# MCU_board_ATmega328p_v2_4.net
KiCad netlist of a schematic drawn in EAGLE
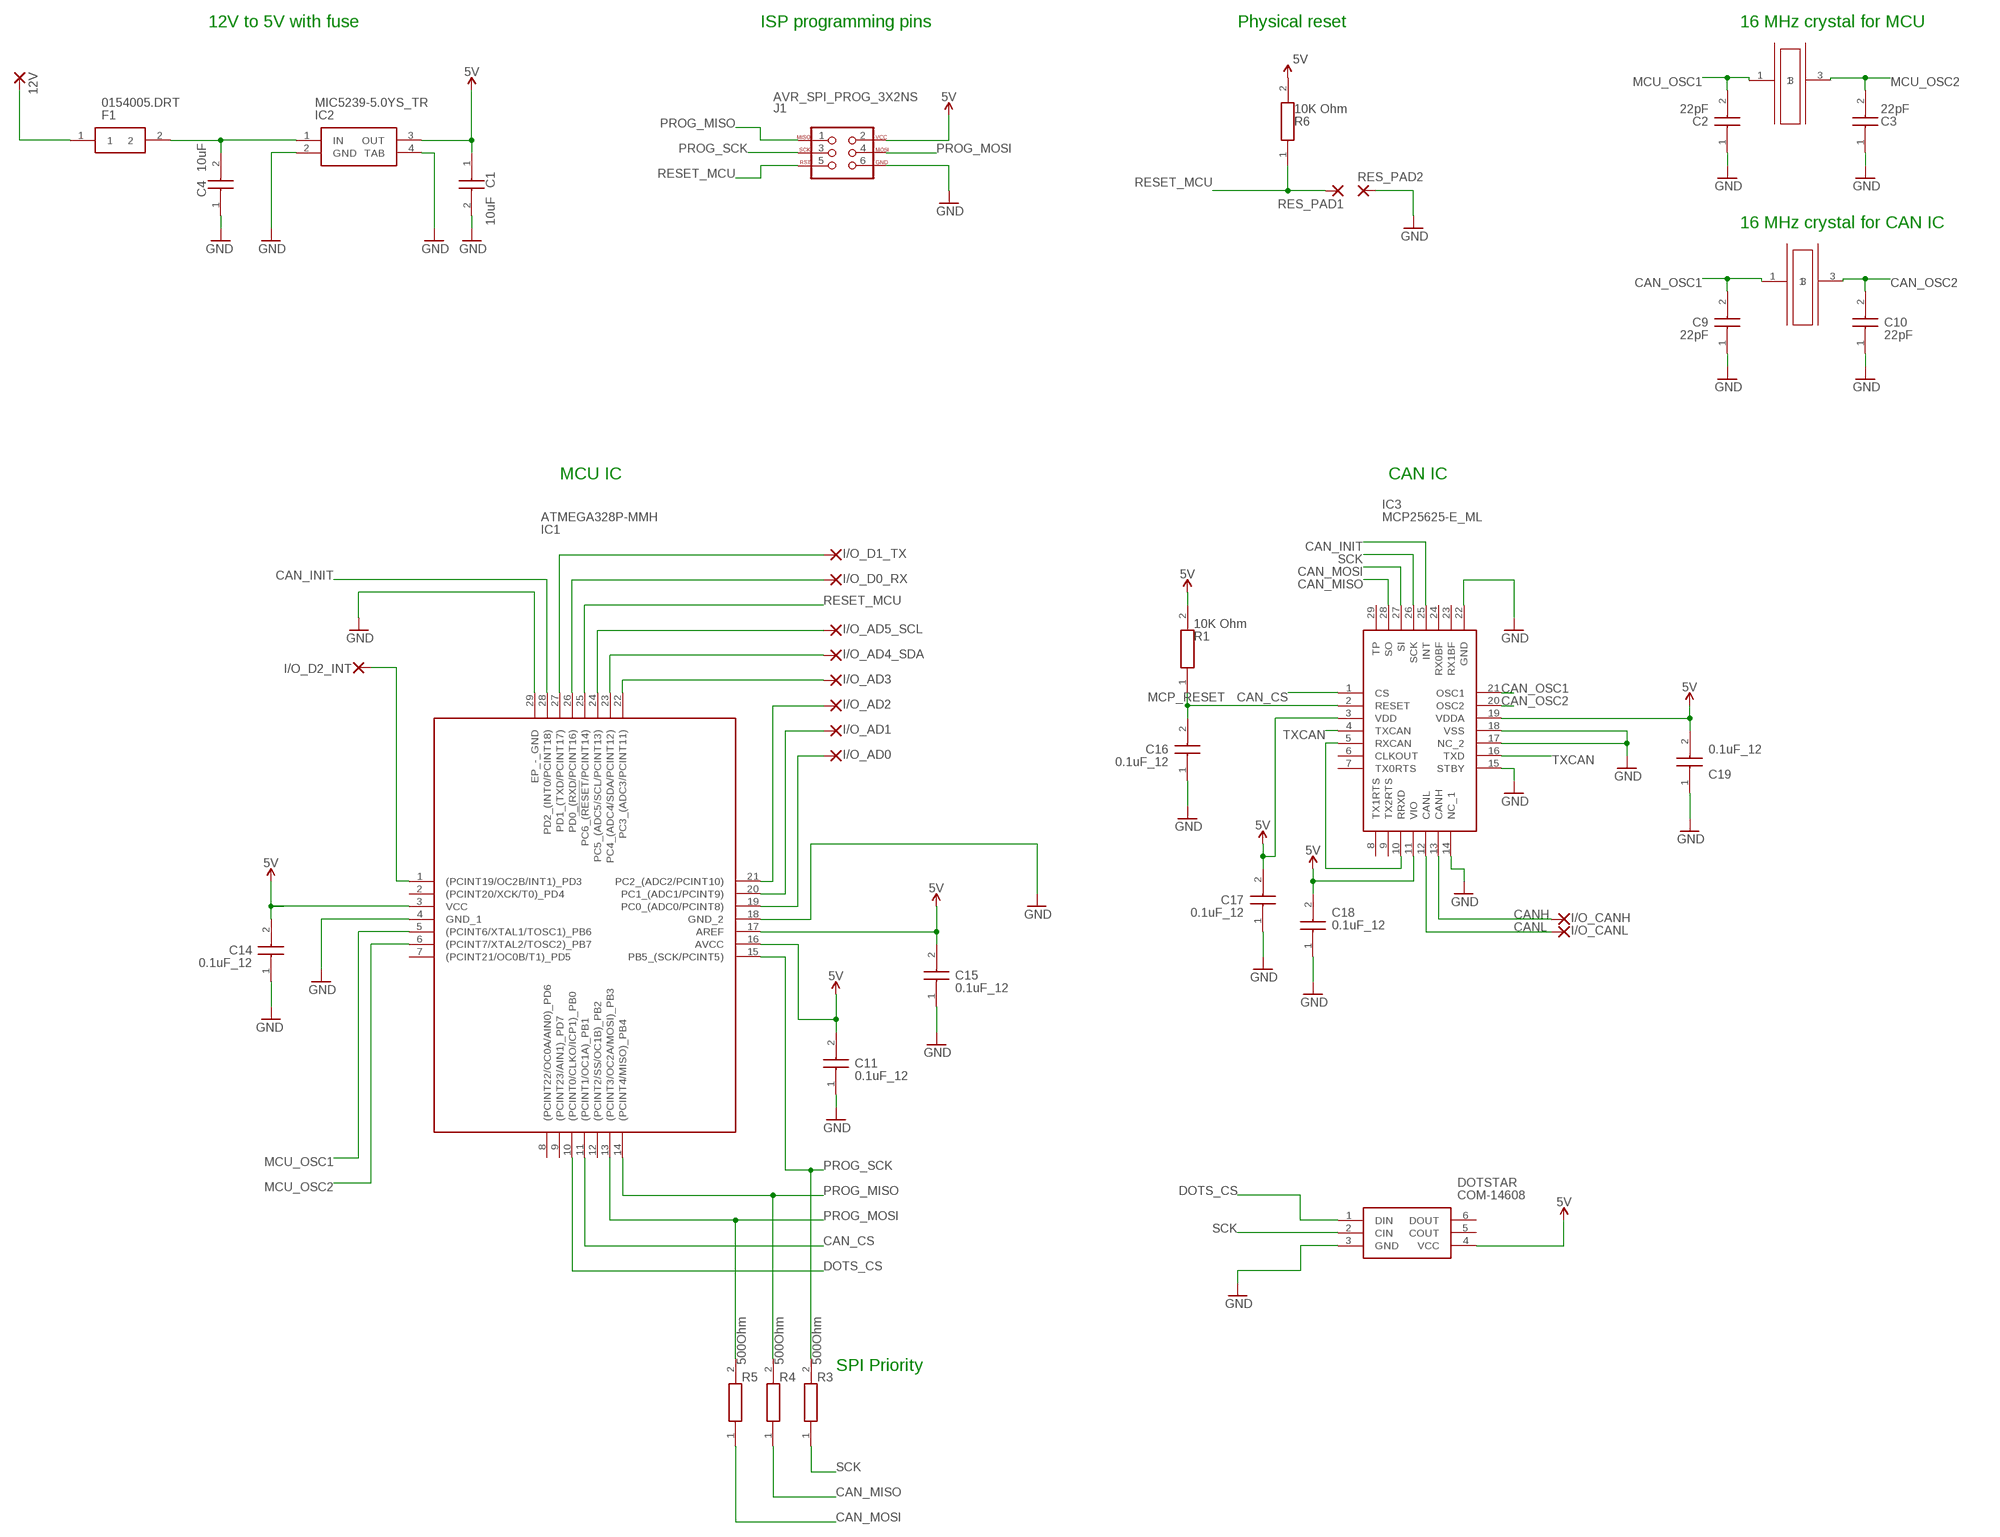
[diagram p0: schematic, sheet 1]

(export (version "E")
  (design (tool "Eeschema 10.0.6"))
  (components
    (comp (ref "12V")
      (value "2,15/1,0(HALFHOLE)H+V")
      (footprint "eagle-import:2,54_2,0(HALFHOLE)H+V")
      (libsource (lib "eagle-import") (part "2,15/1,0(HALFHOLE)H+V"))
    )
    (comp (ref "C1")
      (value "10uF")
      (footprint "eagle-import:CAPPM3216X180N")
      (fields (field (name "ARROW_PART_NUMBER") "T491A106K016AT") (field (name "RS_PART_NUMBER") "1696687"))
      (libsource (lib "eagle-import") (part "T491A106K016AT"))
    )
    (comp (ref "C2")
      (value "22pF")
      (footprint "eagle-import:CAPC3216X229N")
      (fields (field (name "ARROW_PART_NUMBER") "12066D106KAT2A") (field (name "RS_PART_NUMBER") "1356756"))
      (libsource (lib "eagle-import") (part "12066D106KAT2A"))
    )
    (comp (ref "C3")
      (value "22pF")
      (footprint "eagle-import:CAPC3216X229N")
      (fields (field (name "ARROW_PART_NUMBER") "12066D106KAT2A") (field (name "RS_PART_NUMBER") "1356756"))
      (libsource (lib "eagle-import") (part "12066D106KAT2A"))
    )
    (comp (ref "C4")
      (value "10uF")
      (footprint "eagle-import:CAPPM3216X180N")
      (fields (field (name "ARROW_PART_NUMBER") "T491A106K016AT") (field (name "RS_PART_NUMBER") "1696687"))
      (libsource (lib "eagle-import") (part "T491A106K016AT"))
    )
    (comp (ref "C9")
      (value "22pF")
      (footprint "eagle-import:CAPC3216X229N")
      (fields (field (name "ARROW_PART_NUMBER") "12066D106KAT2A") (field (name "RS_PART_NUMBER") "1356756"))
      (libsource (lib "eagle-import") (part "12066D106KAT2A"))
    )
    (comp (ref "C10")
      (value "22pF")
      (footprint "eagle-import:CAPC3216X229N")
      (fields (field (name "ARROW_PART_NUMBER") "12066D106KAT2A") (field (name "RS_PART_NUMBER") "1356756"))
      (libsource (lib "eagle-import") (part "12066D106KAT2A"))
    )
    (comp (ref "C11")
      (value "0.1uF_12")
      (footprint "eagle-import:CAPC3216X229N")
      (fields (field (name "ARROW_PART_NUMBER") "12066D106KAT2A") (field (name "RS_PART_NUMBER") "1356756"))
      (libsource (lib "eagle-import") (part "12066D106KAT2A"))
    )
    (comp (ref "C14")
      (value "0.1uF_12")
      (footprint "eagle-import:CAPC3216X229N")
      (fields (field (name "ARROW_PART_NUMBER") "12066D106KAT2A") (field (name "RS_PART_NUMBER") "1356756"))
      (libsource (lib "eagle-import") (part "12066D106KAT2A"))
    )
    (comp (ref "C15")
      (value "0.1uF_12")
      (footprint "eagle-import:CAPC3216X229N")
      (fields (field (name "ARROW_PART_NUMBER") "12066D106KAT2A") (field (name "RS_PART_NUMBER") "1356756"))
      (libsource (lib "eagle-import") (part "12066D106KAT2A"))
    )
    (comp (ref "C16")
      (value "0.1uF_12")
      (footprint "eagle-import:CAPC3216X229N")
      (fields (field (name "ARROW_PART_NUMBER") "12066D106KAT2A") (field (name "RS_PART_NUMBER") "1356756"))
      (libsource (lib "eagle-import") (part "12066D106KAT2A"))
    )
    (comp (ref "C17")
      (value "0.1uF_12")
      (footprint "eagle-import:CAPC3216X229N")
      (fields (field (name "ARROW_PART_NUMBER") "12066D106KAT2A") (field (name "RS_PART_NUMBER") "1356756"))
      (libsource (lib "eagle-import") (part "12066D106KAT2A"))
    )
    (comp (ref "C18")
      (value "0.1uF_12")
      (footprint "eagle-import:CAPC3216X229N")
      (fields (field (name "ARROW_PART_NUMBER") "12066D106KAT2A") (field (name "RS_PART_NUMBER") "1356756"))
      (libsource (lib "eagle-import") (part "12066D106KAT2A"))
    )
    (comp (ref "C19")
      (value "0.1uF_12")
      (footprint "eagle-import:CAPC3216X229N")
      (fields (field (name "ARROW_PART_NUMBER") "12066D106KAT2A") (field (name "RS_PART_NUMBER") "1356756"))
      (libsource (lib "eagle-import") (part "12066D106KAT2A"))
    )
    (comp (ref "DOTSTAR")
      (value "COM-14608")
      (footprint "eagle-import:SON75P200X200X100-6N")
      (libsource (lib "eagle-import") (part "COM-14608"))
    )
    (comp (ref "F1")
      (value "0154005.DRT")
      (footprint "eagle-import:0154001.DRT")
      (fields (field (name "RS_PART_NUMBER") "2196260P"))
      (libsource (lib "eagle-import") (part "0154005.DRT"))
    )
    (comp (ref "I/O_AD0")
      (value "2,15/1,0(HALFHOLE)H+V")
      (footprint "eagle-import:2,54_2,0(HALFHOLE)H+V")
      (libsource (lib "eagle-import") (part "2,15/1,0(HALFHOLE)H+V"))
    )
    (comp (ref "I/O_AD1")
      (value "2,15/1,0(HALFHOLE)H+V")
      (footprint "eagle-import:2,54_2,0(HALFHOLE)H+V")
      (libsource (lib "eagle-import") (part "2,15/1,0(HALFHOLE)H+V"))
    )
    (comp (ref "I/O_AD2")
      (value "2,15/1,0(HALFHOLE)H+V")
      (footprint "eagle-import:2,54_2,0(HALFHOLE)H+V")
      (libsource (lib "eagle-import") (part "2,15/1,0(HALFHOLE)H+V"))
    )
    (comp (ref "I/O_AD3")
      (value "2,15/1,0(HALFHOLE)H+V")
      (footprint "eagle-import:2,54_2,0(HALFHOLE)H+V")
      (libsource (lib "eagle-import") (part "2,15/1,0(HALFHOLE)H+V"))
    )
    (comp (ref "I/O_AD4_SDA")
      (value "2,15/1,0(HALFHOLE)H+V")
      (footprint "eagle-import:2,54_2,0(HALFHOLE)H+V")
      (libsource (lib "eagle-import") (part "2,15/1,0(HALFHOLE)H+V"))
    )
    (comp (ref "I/O_AD5_SCL")
      (value "2,15/1,0(HALFHOLE)H+V")
      (footprint "eagle-import:2,54_2,0(HALFHOLE)H+V")
      (libsource (lib "eagle-import") (part "2,15/1,0(HALFHOLE)H+V"))
    )
    (comp (ref "I/O_CANH")
      (value "2,15/1,0(HALFHOLE)H+V")
      (footprint "eagle-import:2,54_2,0(HALFHOLE)H+V")
      (libsource (lib "eagle-import") (part "2,15/1,0(HALFHOLE)H+V"))
    )
    (comp (ref "I/O_CANL")
      (value "2,15/1,0(HALFHOLE)H+V")
      (footprint "eagle-import:2,54_2,0(HALFHOLE)H+V")
      (libsource (lib "eagle-import") (part "2,15/1,0(HALFHOLE)H+V"))
    )
    (comp (ref "I/O_D0_RX")
      (value "2,15/1,0(HALFHOLE)H+V")
      (footprint "eagle-import:2,54_2,0(HALFHOLE)H+V")
      (libsource (lib "eagle-import") (part "2,15/1,0(HALFHOLE)H+V"))
    )
    (comp (ref "I/O_D1_TX")
      (value "2,15/1,0(HALFHOLE)H+V")
      (footprint "eagle-import:2,54_2,0(HALFHOLE)H+V")
      (libsource (lib "eagle-import") (part "2,15/1,0(HALFHOLE)H+V"))
    )
    (comp (ref "I/O_D2_INT")
      (value "2,15/1,0(HALFHOLE)H+V")
      (footprint "eagle-import:2,54_2,0(HALFHOLE)H+V")
      (libsource (lib "eagle-import") (part "2,15/1,0(HALFHOLE)H+V"))
    )
    (comp (ref "IC1")
      (value "ATMEGA328P-MMH")
      (footprint "eagle-import:QFN45P400X400X100-29N")
      (fields (field (name "RS_PART_NUMBER") "1310272P"))
      (libsource (lib "eagle-import") (part "ATMEGA328P-MMH"))
    )
    (comp (ref "IC2")
      (value "MIC5239-5.0YS_TR")
      (footprint "eagle-import:SOT230P700X170-4N")
      (fields
        (field (name "ARROW_PART_NUMBER") "MIC5239-5.0YS TR")
        (field (name "RS_PART_NUMBER") "7275535P")
      )
      (libsource (lib "eagle-import") (part "MIC5239-5.0YS_TR"))
    )
    (comp (ref "IC3")
      (value "MCP25625-E_ML")
      (footprint "eagle-import:QFN65P600X600X100-29N")
      (fields (field (name "ARROW_PART_NUMBER") "MCP25625-E/ML") (field (name "RS_PART_NUMBER") "1654104"))
      (libsource (lib "eagle-import") (part "MCP25625-E_ML"))
    )
    (comp (ref "J1")
      (value "AVR_SPI_PROG_3X2NS")
      (footprint "eagle-import:2X3-NS")
      (libsource (lib "eagle-import") (part "AVR_SPI_PROG_3X2NS"))
    )
    (comp (ref "R1")
      (value "10K Ohm")
      (footprint "eagle-import:RESC3116X65N")
      (fields
        (field (name "ARROW_PART_NUMBER") "CRCW120610K0FKEAHP")
        (field (name "RS_PART_NUMBER") "8121789P")
      )
      (libsource (lib "eagle-import") (part "CRCW120610K0FKEAHP"))
    )
    (comp (ref "R3")
      (value "500Ohm")
      (footprint "eagle-import:RESC3116X65N")
      (fields (field (name "ARROW_PART_NUMBER") "CRCW1206499RFKEAHP"))
      (libsource (lib "eagle-import") (part "CRCW1206499RFKEAHP"))
    )
    (comp (ref "R4")
      (value "500Ohm")
      (footprint "eagle-import:RESC3116X65N")
      (fields (field (name "ARROW_PART_NUMBER") "CRCW1206499RFKEAHP"))
      (libsource (lib "eagle-import") (part "CRCW1206499RFKEAHP"))
    )
    (comp (ref "R5")
      (value "500Ohm")
      (footprint "eagle-import:RESC3116X65N")
      (fields (field (name "ARROW_PART_NUMBER") "CRCW1206499RFKEAHP"))
      (libsource (lib "eagle-import") (part "CRCW1206499RFKEAHP"))
    )
    (comp (ref "R6")
      (value "10K Ohm")
      (footprint "eagle-import:RESC3116X65N")
      (fields
        (field (name "ARROW_PART_NUMBER") "CRCW120610K0FKEAHP")
        (field (name "RS_PART_NUMBER") "8121789P")
      )
      (libsource (lib "eagle-import") (part "CRCW120610K0FKEAHP"))
    )
    (comp (ref "RES_PAD1")
      (value "SMD2")
      (footprint "eagle-import:SMD1,27-2,54")
      (libsource (lib "eagle-import") (part "SMD2"))
    )
    (comp (ref "RES_PAD2")
      (value "SMD2")
      (footprint "eagle-import:SMD1,27-2,54")
      (libsource (lib "eagle-import") (part "SMD2"))
    )
    (comp (ref "U$1")
      (value "FA-20H")
      (footprint "eagle-import:FA-20H")
      (libsource (lib "eagle-import") (part "FA-20H"))
    )
    (comp (ref "U$2")
      (value "FA-20H")
      (footprint "eagle-import:FA-20H")
      (libsource (lib "eagle-import") (part "FA-20H"))
    )
  )
  (nets
    (net (code "1") (name "/CANH") (class "Default")
      (node (ref "I/O_CANH") (pin "P$1") (pinfunction "P_P$1") (pintype "passive"))
      (node (ref "IC3") (pin "13") (pinfunction "CANH_13") (pintype "bidirectional"))
    )
    (net (code "2") (name "/CANL") (class "Default")
      (node (ref "I/O_CANL") (pin "P$1") (pinfunction "P_P$1") (pintype "passive"))
      (node (ref "IC3") (pin "12") (pinfunction "CANL_12") (pintype "bidirectional"))
    )
    (net (code "3") (name "/CAN_CS") (class "Default")
      (node (ref "IC1") (pin "11") (pinfunction "(PCINT1/OC1A)_PB1_11") (pintype "bidirectional"))
      (node (ref "IC3") (pin "1") (pinfunction "CS_1") (pintype "input"))
    )
    (net (code "4") (name "/CAN_INIT") (class "Default")
      (node (ref "IC1") (pin "28") (pinfunction "PD2_(INT0/PCINT18)_28") (pintype "bidirectional"))
      (node (ref "IC3") (pin "25") (pinfunction "INT_25") (pintype "input"))
    )
    (net (code "5") (name "/CAN_MISO") (class "Default")
      (node (ref "IC3") (pin "28") (pinfunction "SO_28") (pintype "bidirectional"))
      (node (ref "R4") (pin "1") (pinfunction "1_1") (pintype "bidirectional"))
    )
    (net (code "6") (name "/CAN_MOSI") (class "Default")
      (node (ref "IC3") (pin "27") (pinfunction "SI_27") (pintype "bidirectional"))
      (node (ref "R5") (pin "1") (pinfunction "1_1") (pintype "bidirectional"))
    )
    (net (code "7") (name "/CAN_OSC1") (class "Default")
      (node (ref "C9") (pin "2") (pinfunction "2_2") (pintype "bidirectional"))
      (node (ref "IC3") (pin "21") (pinfunction "OSC1_21") (pintype "bidirectional"))
      (node (ref "U$1") (pin "1") (pinfunction "1_1") (pintype "bidirectional"))
    )
    (net (code "8") (name "/CAN_OSC2") (class "Default")
      (node (ref "C10") (pin "2") (pinfunction "2_2") (pintype "bidirectional"))
      (node (ref "IC3") (pin "20") (pinfunction "OSC2_20") (pintype "bidirectional"))
      (node (ref "U$1") (pin "3") (pinfunction "3_3") (pintype "bidirectional"))
    )
    (net (code "9") (name "/DOTS_CS") (class "Default")
      (node (ref "DOTSTAR") (pin "1") (pinfunction "DIN_1") (pintype "bidirectional"))
      (node (ref "IC1") (pin "10") (pinfunction "(PCINT0/CLKO/ICP1)_PB0_10") (pintype "bidirectional"))
    )
    (net (code "10") (name "/MCP_RESET") (class "Default")
      (node (ref "C16") (pin "2") (pinfunction "2_2") (pintype "bidirectional"))
      (node (ref "IC3") (pin "2") (pinfunction "RESET_2") (pintype "bidirectional"))
      (node (ref "R1") (pin "1") (pinfunction "1_1") (pintype "bidirectional"))
    )
    (net (code "11") (name "/MCU_OSC1") (class "Default")
      (node (ref "C2") (pin "2") (pinfunction "2_2") (pintype "bidirectional"))
      (node (ref "IC1") (pin "5") (pinfunction "(PCINT6/XTAL1/TOSC1)_PB6_5") (pintype "bidirectional"))
      (node (ref "U$2") (pin "1") (pinfunction "1_1") (pintype "bidirectional"))
    )
    (net (code "12") (name "/MCU_OSC2") (class "Default")
      (node (ref "C3") (pin "2") (pinfunction "2_2") (pintype "bidirectional"))
      (node (ref "IC1") (pin "6") (pinfunction "(PCINT7/XTAL2/TOSC2)_PB7_6") (pintype "bidirectional"))
      (node (ref "U$2") (pin "3") (pinfunction "3_3") (pintype "bidirectional"))
    )
    (net (code "13") (name "/PROG_MISO") (class "Default")
      (node (ref "IC1") (pin "14") (pinfunction "(PCINT4/MISO)_PB4_14") (pintype "bidirectional"))
      (node (ref "J1") (pin "1") (pinfunction "1_1") (pintype "passive"))
      (node (ref "R4") (pin "2") (pinfunction "2_2") (pintype "bidirectional"))
    )
    (net (code "14") (name "/PROG_MOSI") (class "Default")
      (node (ref "IC1") (pin "13") (pinfunction "(PCINT3/OC2A/MOSI)_PB3_13") (pintype "bidirectional"))
      (node (ref "J1") (pin "4") (pinfunction "4_4") (pintype "passive"))
      (node (ref "R5") (pin "2") (pinfunction "2_2") (pintype "bidirectional"))
    )
    (net (code "15") (name "/PROG_SCK") (class "Default")
      (node (ref "IC1") (pin "15") (pinfunction "PB5_(SCK/PCINT5)_15") (pintype "bidirectional"))
      (node (ref "J1") (pin "3") (pinfunction "3_3") (pintype "passive"))
      (node (ref "R3") (pin "2") (pinfunction "2_2") (pintype "bidirectional"))
    )
    (net (code "16") (name "/RESET_MCU") (class "Default")
      (node (ref "IC1") (pin "25") (pinfunction "PC6_(~{RESET}/PCINT14)_25") (pintype "bidirectional"))
      (node (ref "J1") (pin "5") (pinfunction "5_5") (pintype "passive"))
      (node (ref "R6") (pin "1") (pinfunction "1_1") (pintype "bidirectional"))
      (node (ref "RES_PAD1") (pin "1") (pinfunction "P_1") (pintype "passive"))
    )
    (net (code "17") (name "/SCK") (class "Default")
      (node (ref "DOTSTAR") (pin "2") (pinfunction "CIN_2") (pintype "bidirectional"))
      (node (ref "IC3") (pin "26") (pinfunction "SCK_26") (pintype "bidirectional"))
      (node (ref "R3") (pin "1") (pinfunction "1_1") (pintype "bidirectional"))
    )
    (net (code "18") (name "/TXCAN") (class "Default")
      (node (ref "IC3") (pin "16") (pinfunction "TXD_16") (pintype "bidirectional"))
      (node (ref "IC3") (pin "4") (pinfunction "TXCAN_4") (pintype "bidirectional"))
    )
    (net (code "19") (name "5V") (class "Default")
      (node (ref "C1") (pin "1") (pinfunction "K_1") (pintype "bidirectional"))
      (node (ref "C11") (pin "2") (pinfunction "2_2") (pintype "bidirectional"))
      (node (ref "C14") (pin "2") (pinfunction "2_2") (pintype "bidirectional"))
      (node (ref "C15") (pin "2") (pinfunction "2_2") (pintype "bidirectional"))
      (node (ref "C17") (pin "2") (pinfunction "2_2") (pintype "bidirectional"))
      (node (ref "C18") (pin "2") (pinfunction "2_2") (pintype "bidirectional"))
      (node (ref "C19") (pin "2") (pinfunction "2_2") (pintype "bidirectional"))
      (node (ref "DOTSTAR") (pin "4") (pinfunction "VCC_4") (pintype "bidirectional"))
      (node (ref "IC1") (pin "16") (pinfunction "AVCC_16") (pintype "bidirectional"))
      (node (ref "IC1") (pin "17") (pinfunction "AREF_17") (pintype "bidirectional"))
      (node (ref "IC1") (pin "3") (pinfunction "VCC_3") (pintype "bidirectional"))
      (node (ref "IC2") (pin "3") (pinfunction "OUT_3") (pintype "bidirectional"))
      (node (ref "IC3") (pin "11") (pinfunction "VIO_11") (pintype "bidirectional"))
      (node (ref "IC3") (pin "19") (pinfunction "VDDA_19") (pintype "power_in"))
      (node (ref "IC3") (pin "3") (pinfunction "VDD_3") (pintype "power_in"))
      (node (ref "J1") (pin "2") (pinfunction "2_2") (pintype "passive"))
      (node (ref "R1") (pin "2") (pinfunction "2_2") (pintype "bidirectional"))
      (node (ref "R6") (pin "2") (pinfunction "2_2") (pintype "bidirectional"))
    )
    (net (code "20") (name "GND") (class "Default")
      (node (ref "C1") (pin "2") (pinfunction "A_2") (pintype "bidirectional"))
      (node (ref "C10") (pin "1") (pinfunction "1_1") (pintype "bidirectional"))
      (node (ref "C11") (pin "1") (pinfunction "1_1") (pintype "bidirectional"))
      (node (ref "C14") (pin "1") (pinfunction "1_1") (pintype "bidirectional"))
      (node (ref "C15") (pin "1") (pinfunction "1_1") (pintype "bidirectional"))
      (node (ref "C16") (pin "1") (pinfunction "1_1") (pintype "bidirectional"))
      (node (ref "C17") (pin "1") (pinfunction "1_1") (pintype "bidirectional"))
      (node (ref "C18") (pin "1") (pinfunction "1_1") (pintype "bidirectional"))
      (node (ref "C19") (pin "1") (pinfunction "1_1") (pintype "bidirectional"))
      (node (ref "C2") (pin "1") (pinfunction "1_1") (pintype "bidirectional"))
      (node (ref "C3") (pin "1") (pinfunction "1_1") (pintype "bidirectional"))
      (node (ref "C4") (pin "1") (pinfunction "K_1") (pintype "bidirectional"))
      (node (ref "C9") (pin "1") (pinfunction "1_1") (pintype "bidirectional"))
      (node (ref "DOTSTAR") (pin "3") (pinfunction "GND_3") (pintype "bidirectional"))
      (node (ref "IC1") (pin "18") (pinfunction "GND_2_18") (pintype "bidirectional"))
      (node (ref "IC1") (pin "29") (pinfunction "EP_-_GND_29") (pintype "bidirectional"))
      (node (ref "IC1") (pin "4") (pinfunction "GND_1_4") (pintype "bidirectional"))
      (node (ref "IC2") (pin "2") (pinfunction "GND_2") (pintype "bidirectional"))
      (node (ref "IC2") (pin "4") (pinfunction "TAB_4") (pintype "bidirectional"))
      (node (ref "IC3") (pin "14") (pinfunction "NC_1_14") (pintype "bidirectional"))
      (node (ref "IC3") (pin "15") (pinfunction "STBY_15") (pintype "bidirectional"))
      (node (ref "IC3") (pin "17") (pinfunction "NC_2_17") (pintype "bidirectional"))
      (node (ref "IC3") (pin "18") (pinfunction "VSS_18") (pintype "power_in"))
      (node (ref "IC3") (pin "22") (pinfunction "GND_22") (pintype "power_in"))
      (node (ref "J1") (pin "6") (pinfunction "6_6") (pintype "passive"))
      (node (ref "RES_PAD2") (pin "1") (pinfunction "P_1") (pintype "passive"))
    )
    (net (code "21") (name "Net-(12V-P)") (class "Default")
      (node (ref "12V") (pin "P$1") (pinfunction "P_P$1") (pintype "passive"))
      (node (ref "F1") (pin "1") (pinfunction "1_1") (pintype "bidirectional"))
    )
    (net (code "22") (name "Net-(C4-A)") (class "Default")
      (node (ref "C4") (pin "2") (pinfunction "A_2") (pintype "bidirectional"))
      (node (ref "F1") (pin "2") (pinfunction "2_2") (pintype "bidirectional"))
      (node (ref "IC2") (pin "1") (pinfunction "IN_1") (pintype "bidirectional"))
    )
    (net (code "23") (name "Net-(I/O_AD0-P)") (class "Default")
      (node (ref "I/O_AD0") (pin "P$1") (pinfunction "P_P$1") (pintype "passive"))
      (node (ref "IC1") (pin "19") (pinfunction "PC0_(ADC0/PCINT8)_19") (pintype "bidirectional"))
    )
    (net (code "24") (name "Net-(I/O_AD1-P)") (class "Default")
      (node (ref "I/O_AD1") (pin "P$1") (pinfunction "P_P$1") (pintype "passive"))
      (node (ref "IC1") (pin "20") (pinfunction "PC1_(ADC1/PCINT9)_20") (pintype "bidirectional"))
    )
    (net (code "25") (name "Net-(I/O_AD2-P)") (class "Default")
      (node (ref "I/O_AD2") (pin "P$1") (pinfunction "P_P$1") (pintype "passive"))
      (node (ref "IC1") (pin "21") (pinfunction "PC2_(ADC2/PCINT10)_21") (pintype "bidirectional"))
    )
    (net (code "26") (name "Net-(I/O_AD3-P)") (class "Default")
      (node (ref "I/O_AD3") (pin "P$1") (pinfunction "P_P$1") (pintype "passive"))
      (node (ref "IC1") (pin "22") (pinfunction "PC3_(ADC3/PCINT11)_22") (pintype "bidirectional"))
    )
    (net (code "27") (name "Net-(I/O_AD4_SDA-P)") (class "Default")
      (node (ref "I/O_AD4_SDA") (pin "P$1") (pinfunction "P_P$1") (pintype "passive"))
      (node (ref "IC1") (pin "23") (pinfunction "PC4_(ADC4/SDA/PCINT12)_23") (pintype "bidirectional"))
    )
    (net (code "28") (name "Net-(I/O_AD5_SCL-P)") (class "Default")
      (node (ref "I/O_AD5_SCL") (pin "P$1") (pinfunction "P_P$1") (pintype "passive"))
      (node (ref "IC1") (pin "24") (pinfunction "PC5_(ADC5/SCL/PCINT13)_24") (pintype "bidirectional"))
    )
    (net (code "29") (name "Net-(I/O_D0_RX-P)") (class "Default")
      (node (ref "I/O_D0_RX") (pin "P$1") (pinfunction "P_P$1") (pintype "passive"))
      (node (ref "IC1") (pin "26") (pinfunction "PD0_(RXD/PCINT16)_26") (pintype "bidirectional"))
    )
    (net (code "30") (name "Net-(I/O_D1_TX-P)") (class "Default")
      (node (ref "I/O_D1_TX") (pin "P$1") (pinfunction "P_P$1") (pintype "passive"))
      (node (ref "IC1") (pin "27") (pinfunction "PD1_(TXD/PCINT17)_27") (pintype "bidirectional"))
    )
    (net (code "31") (name "Net-(I/O_D2_INT-P)") (class "Default")
      (node (ref "I/O_D2_INT") (pin "P$1") (pinfunction "P_P$1") (pintype "passive"))
      (node (ref "IC1") (pin "1") (pinfunction "(PCINT19/OC2B/INT1)_PD3_1") (pintype "bidirectional"))
    )
    (net (code "32") (name "Net-(IC3-RRXD)") (class "Default")
      (node (ref "IC3") (pin "10") (pinfunction "RRXD_10") (pintype "bidirectional"))
      (node (ref "IC3") (pin "5") (pinfunction "RXCAN_5") (pintype "bidirectional"))
    )
    (net (code "33") (name "unconnected-(DOTSTAR-COUT-Pad5)") (class "Default")
      (node (ref "DOTSTAR") (pin "5") (pinfunction "COUT_5") (pintype "bidirectional"))
    )
    (net (code "34") (name "unconnected-(DOTSTAR-DOUT-Pad6)") (class "Default")
      (node (ref "DOTSTAR") (pin "6") (pinfunction "DOUT_6") (pintype "bidirectional"))
    )
    (net (code "35") (name "unconnected-(IC1-(PCINT2{slash}SS{slash}OC1B)_PB2-Pad12)") (class "Default")
      (node (ref "IC1") (pin "12") (pinfunction "(PCINT2/SS/OC1B)_PB2_12") (pintype "bidirectional"))
    )
    (net (code "36") (name "unconnected-(IC1-(PCINT20{slash}XCK{slash}T0)_PD4-Pad2)") (class "Default")
      (node (ref "IC1") (pin "2") (pinfunction "(PCINT20/XCK/T0)_PD4_2") (pintype "bidirectional"))
    )
    (net (code "37") (name "unconnected-(IC1-(PCINT21{slash}OC0B{slash}T1)_PD5-Pad7)") (class "Default")
      (node (ref "IC1") (pin "7") (pinfunction "(PCINT21/OC0B/T1)_PD5_7") (pintype "bidirectional"))
    )
    (net (code "38") (name "unconnected-(IC1-(PCINT22{slash}OC0A{slash}AIN0)_PD6-Pad8)") (class "Default")
      (node (ref "IC1") (pin "8") (pinfunction "(PCINT22/OC0A/AIN0)_PD6_8") (pintype "bidirectional"))
    )
    (net (code "39") (name "unconnected-(IC1-(PCINT23{slash}AIN1)_PD7-Pad9)") (class "Default")
      (node (ref "IC1") (pin "9") (pinfunction "(PCINT23/AIN1)_PD7_9") (pintype "bidirectional"))
    )
    (net (code "40") (name "unconnected-(IC3-CLKOUT-Pad6)") (class "Default")
      (node (ref "IC3") (pin "6") (pinfunction "CLKOUT_6") (pintype "output"))
    )
    (net (code "41") (name "unconnected-(IC3-RX0BF-Pad24)") (class "Default")
      (node (ref "IC3") (pin "24") (pinfunction "RX0BF_24") (pintype "bidirectional"))
    )
    (net (code "42") (name "unconnected-(IC3-RX1BF-Pad23)") (class "Default")
      (node (ref "IC3") (pin "23") (pinfunction "RX1BF_23") (pintype "bidirectional"))
    )
    (net (code "43") (name "unconnected-(IC3-TP-Pad29)") (class "Default")
      (node (ref "IC3") (pin "29") (pinfunction "TP_29") (pintype "bidirectional"))
    )
    (net (code "44") (name "unconnected-(IC3-TX0RTS-Pad7)") (class "Default")
      (node (ref "IC3") (pin "7") (pinfunction "TX0RTS_7") (pintype "bidirectional"))
    )
    (net (code "45") (name "unconnected-(IC3-TX1RTS-Pad8)") (class "Default")
      (node (ref "IC3") (pin "8") (pinfunction "TX1RTS_8") (pintype "bidirectional"))
    )
    (net (code "46") (name "unconnected-(IC3-TX2RTS-Pad9)") (class "Default")
      (node (ref "IC3") (pin "9") (pinfunction "TX2RTS_9") (pintype "bidirectional"))
    )
  )
)
